# MainSheet.net
KiCad netlist of a schematic drawn in Altium Designer
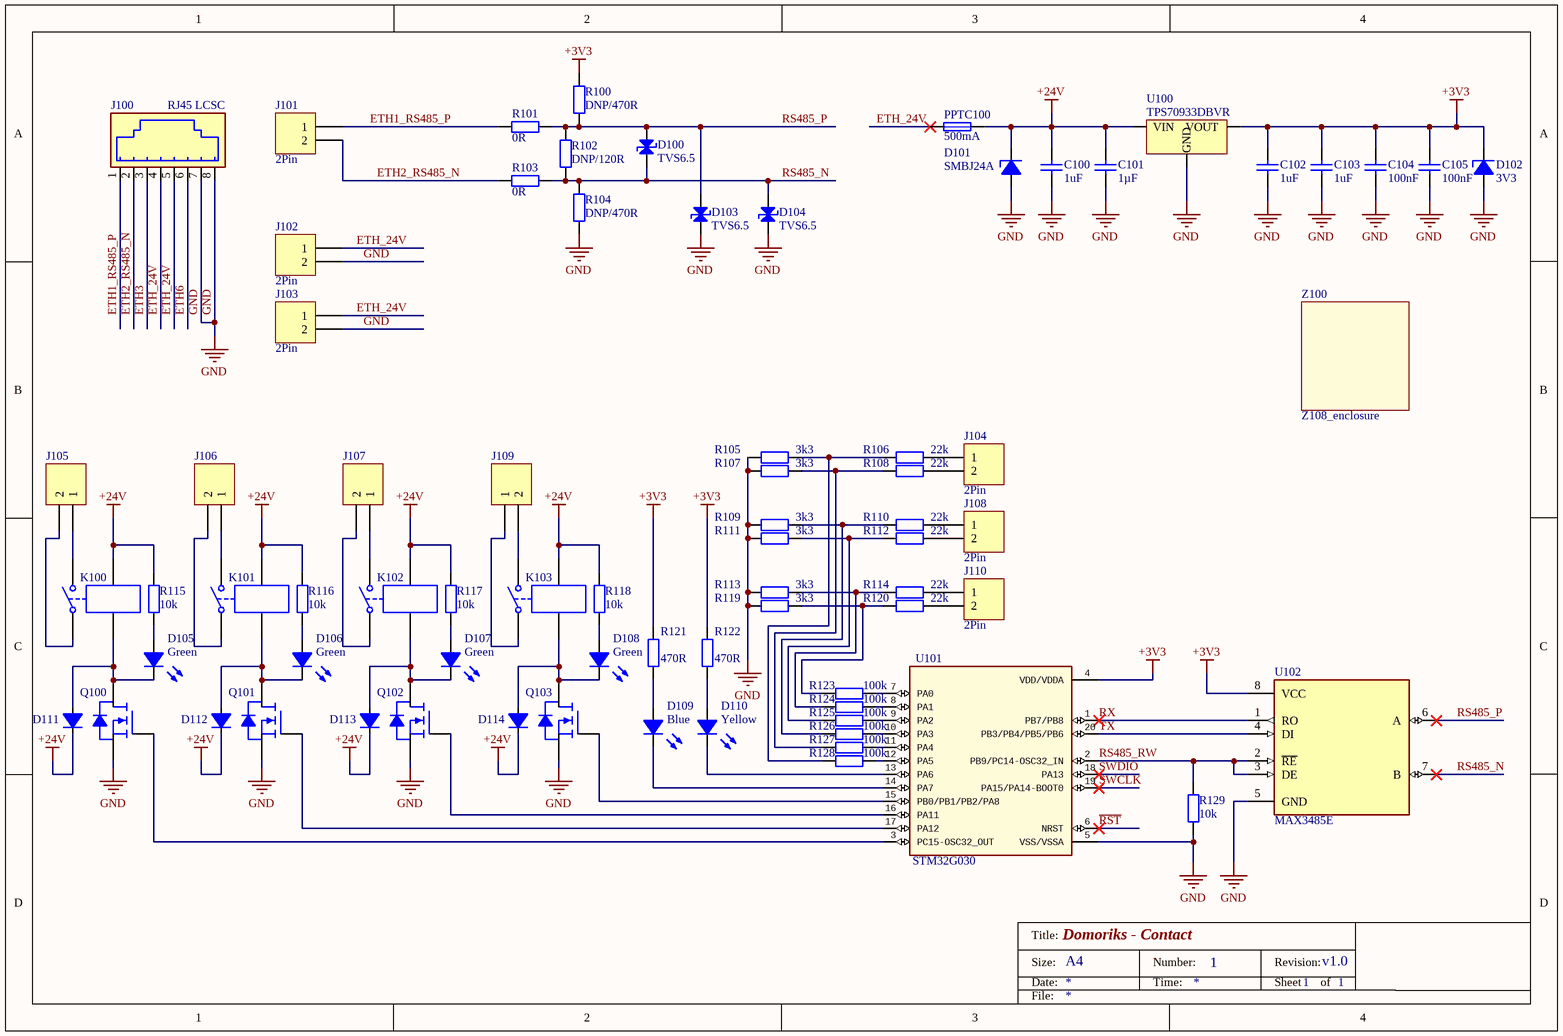
[diagram p0: MainSheet.SchDoc]

(export (version "E")
  (design (tool "Eeschema 10.0.6"))
  (components
    (comp (ref "C100") (value "1uF") (footprint "C0603") (libsource (lib "MyLib") (part "Capacitor")))
    (comp (ref "C101") (value "1µF") (footprint "C0603") (libsource (lib "MyLib") (part "Capacitor")))
    (comp (ref "C102") (value "1uF") (footprint "C0603") (libsource (lib "MyLib") (part "Capacitor")))
    (comp (ref "C103") (value "1uF") (footprint "C0603") (libsource (lib "MyLib") (part "Capacitor")))
    (comp (ref "C104") (value "100nF") (footprint "C0603") (libsource (lib "MyLib") (part "Capacitor")))
    (comp (ref "C105") (value "100nF") (footprint "C0603") (libsource (lib "MyLib") (part "Capacitor")))
    (comp (ref "D100") (value "TVS6.5") (footprint "SOD323") (libsource (lib "MyLib") (part "TVS Bi")))
    (comp (ref "D101") (value "SMBJ24A") (footprint "SMB") (libsource (lib "MyLib") (part "TVS Uni")))
    (comp (ref "D102") (value "3V3") (footprint "SOD323") (libsource (lib "MyLib") (part "TVS Uni")))
    (comp (ref "D103") (value "TVS6.5") (footprint "SOD323") (libsource (lib "MyLib") (part "TVS Bi")))
    (comp (ref "D104") (value "TVS6.5") (footprint "SOD323") (libsource (lib "MyLib") (part "TVS Bi")))
    (comp (ref "D105") (value "Green") (footprint "LED_0603_G") (libsource (lib "MyLib") (part "Led")))
    (comp (ref "D106") (value "Green") (footprint "LED_0603_G") (libsource (lib "MyLib") (part "Led")))
    (comp (ref "D107") (value "Green") (footprint "LED_0603_G") (libsource (lib "MyLib") (part "Led")))
    (comp (ref "D108") (value "Green") (footprint "LED_0603_G") (libsource (lib "MyLib") (part "Led")))
    (comp (ref "D109") (value "Blue") (footprint "LED_0603_B") (libsource (lib "MyLib") (part "Led")))
    (comp (ref "D110") (value "Yellow") (footprint "LED_0603_G") (libsource (lib "MyLib") (part "Led")))
    (comp (ref "D111") (value "Diode") (footprint "SOD323") (libsource (lib "MyLib") (part "Diode")))
    (comp (ref "D112") (value "Diode") (footprint "SOD323") (libsource (lib "MyLib") (part "Diode")))
    (comp (ref "D113") (value "Diode") (footprint "SOD323") (libsource (lib "MyLib") (part "Diode")))
    (comp (ref "D114") (value "Diode") (footprint "SOD323") (libsource (lib "MyLib") (part "Diode")))
    (comp (ref "J100")
      (value "RJ45 LCSC")
      (footprint "RJ45_RA")
      (description "Jack Modular Connector 8p8c (RJ45, Ethernet) Vertical Unshielded Cat5")
      (fields (field (name "MF") "Wurth Elektronik") (field (name "MP") "615008144221"))
      (libsource (lib "MyLib") (part "RJ45 LCSC"))
    )
    (comp (ref "J101") (value "2Pin") (footprint "WURTH_691216710002") (libsource (lib "") (part "2Pin_1")))
    (comp (ref "J102") (value "2Pin") (footprint "WURTH_691216710002") (libsource (lib "") (part "2Pin_1")))
    (comp (ref "J103") (value "2Pin") (footprint "WURTH_691216710002") (libsource (lib "") (part "2Pin_1")))
    (comp (ref "J104")
      (value "2Pin")
      (footprint "WURTH_691216710002")
      (libsource (lib "MyLib") (part "2Pin"))
    )
    (comp (ref "J105")
      (value "2Pin")
      (footprint "WURTH_691216910002")
      (libsource (lib "MyLib") (part "2Pin"))
    )
    (comp (ref "J106")
      (value "2Pin")
      (footprint "WURTH_691216910002")
      (libsource (lib "MyLib") (part "2Pin"))
    )
    (comp (ref "J107")
      (value "2Pin")
      (footprint "WURTH_691216910002")
      (libsource (lib "MyLib") (part "2Pin"))
    )
    (comp (ref "J108")
      (value "2Pin")
      (footprint "WURTH_691216710002")
      (libsource (lib "MyLib") (part "2Pin"))
    )
    (comp (ref "J109") (value "2Pin") (footprint "WURTH_691216910002") (libsource (lib "") (part "2Pin_2")))
    (comp (ref "J110")
      (value "2Pin")
      (footprint "WURTH_691216710002")
      (libsource (lib "MyLib") (part "2Pin"))
    )
    (comp (ref "K100")
      (value "Relay-SPST")
      (footprint "G5RL-1A-E-HR")
      (description "Single-Pole Single-Throw Relay")
      (fields (field (name "PUBLISHER") "Altium Limited"))
      (libsource (lib "MyLib") (part "Relay-SPST"))
    )
    (comp (ref "K101")
      (value "Relay-SPST")
      (footprint "G5RL-1A-E-HR")
      (description "Single-Pole Single-Throw Relay")
      (fields (field (name "PUBLISHER") "Altium Limited"))
      (libsource (lib "MyLib") (part "Relay-SPST"))
    )
    (comp (ref "K102")
      (value "Relay-SPST")
      (footprint "G5RL-1A-E-HR")
      (description "Single-Pole Single-Throw Relay")
      (fields (field (name "PUBLISHER") "Altium Limited"))
      (libsource (lib "MyLib") (part "Relay-SPST"))
    )
    (comp (ref "K103")
      (value "Relay-SPST")
      (footprint "G5RL-1A-E-HR")
      (description "Single-Pole Single-Throw Relay")
      (fields (field (name "PUBLISHER") "Altium Limited"))
      (libsource (lib "MyLib") (part "Relay-SPST"))
    )
    (comp (ref "PPTC100")
      (value "500mA")
      (footprint "PPTC1812")
      (description "Polymeric PTC Resettable Fuse 24V 500mA Ih Surface Mount 1812 _4532 Metric_, Concave")
      (fields (field (name "MP") "MINISMDC050F-2") (field (name "MF") "Littelfuse Inc."))
      (libsource (lib "MyLib") (part "PPTC"))
    )
    (comp (ref "Q100") (value "N-FET") (footprint "SOT323") (libsource (lib "MyLib") (part "N-FET")))
    (comp (ref "Q101") (value "N-FET") (footprint "SOT323") (libsource (lib "MyLib") (part "N-FET")))
    (comp (ref "Q102") (value "N-FET") (footprint "SOT323") (libsource (lib "MyLib") (part "N-FET")))
    (comp (ref "Q103") (value "N-FET") (footprint "SOT323") (libsource (lib "MyLib") (part "N-FET")))
    (comp (ref "R100") (value "DNP/470R") (footprint "R0603") (libsource (lib "MyLib") (part "Resistor")))
    (comp (ref "R101") (value "0R") (footprint "R0603") (libsource (lib "") (part "Resistor_1")))
    (comp (ref "R102") (value "DNP/120R") (footprint "R0603") (libsource (lib "MyLib") (part "Resistor")))
    (comp (ref "R103") (value "0R") (footprint "R0603") (libsource (lib "") (part "Resistor_1")))
    (comp (ref "R104") (value "DNP/470R") (footprint "R0603") (libsource (lib "MyLib") (part "Resistor")))
    (comp (ref "R105") (value "3k3") (footprint "R0603") (libsource (lib "") (part "Resistor_1")))
    (comp (ref "R106") (value "22k") (footprint "R0603") (libsource (lib "") (part "Resistor_1")))
    (comp (ref "R107") (value "3k3") (footprint "R0603") (libsource (lib "") (part "Resistor_1")))
    (comp (ref "R108") (value "22k") (footprint "R0603") (libsource (lib "") (part "Resistor_1")))
    (comp (ref "R109") (value "3k3") (footprint "R0603") (libsource (lib "") (part "Resistor_1")))
    (comp (ref "R110") (value "22k") (footprint "R0603") (libsource (lib "") (part "Resistor_1")))
    (comp (ref "R111") (value "3k3") (footprint "R0603") (libsource (lib "") (part "Resistor_1")))
    (comp (ref "R112") (value "22k") (footprint "R0603") (libsource (lib "") (part "Resistor_1")))
    (comp (ref "R113") (value "3k3") (footprint "R0603") (libsource (lib "") (part "Resistor_1")))
    (comp (ref "R114") (value "22k") (footprint "R0603") (libsource (lib "") (part "Resistor_1")))
    (comp (ref "R115") (value "10k") (footprint "R0402") (libsource (lib "MyLib") (part "Resistor")))
    (comp (ref "R116") (value "10k") (footprint "R0402") (libsource (lib "MyLib") (part "Resistor")))
    (comp (ref "R117") (value "10k") (footprint "R0402") (libsource (lib "MyLib") (part "Resistor")))
    (comp (ref "R118") (value "10k") (footprint "R0402") (libsource (lib "MyLib") (part "Resistor")))
    (comp (ref "R119") (value "3k3") (footprint "R0603") (libsource (lib "") (part "Resistor_1")))
    (comp (ref "R120") (value "22k") (footprint "R0603") (libsource (lib "") (part "Resistor_1")))
    (comp (ref "R121") (value "470R") (footprint "R0603") (libsource (lib "MyLib") (part "Resistor")))
    (comp (ref "R122") (value "470R") (footprint "R0603") (libsource (lib "MyLib") (part "Resistor")))
    (comp (ref "R123") (value "100k") (footprint "R0603") (libsource (lib "") (part "Resistor_1")))
    (comp (ref "R124") (value "100k") (footprint "R0603") (libsource (lib "") (part "Resistor_1")))
    (comp (ref "R125") (value "100k") (footprint "R0603") (libsource (lib "") (part "Resistor_1")))
    (comp (ref "R126") (value "100k") (footprint "R0603") (libsource (lib "") (part "Resistor_1")))
    (comp (ref "R127") (value "100k") (footprint "R0603") (libsource (lib "") (part "Resistor_1")))
    (comp (ref "R128") (value "100k") (footprint "R0603") (libsource (lib "") (part "Resistor_1")))
    (comp (ref "R129") (value "10k") (footprint "R0603") (libsource (lib "") (part "Resistor_1")))
    (comp (ref "U100")
      (value "TPS70933DBVR")
      (footprint "SOT-23-5")
      (fields (field (name "MP") "LP38690DT-5.0/NOPB") (field (name "MF") "Texas Instruments"))
      (libsource (lib "MyLib") (part "LDO"))
    )
    (comp (ref "U101")
      (value "STM32G030")
      (footprint "TSSOP20")
      (fields
        (field (name "MANUFACTURER_PART_NUMBER") "STM32G030F6P6TR")
        (field (name "COPYRIGHT") "Copyright (C) 2022 Ultra Librarian. All rights reserved.")
      )
      (libsource (lib "MyLib") (part "STM32G030"))
    )
    (comp (ref "U102")
      (value "MAX3485E")
      (footprint "SOIC-08_DOMO")
      (description "1/1 Transceiver Half RS422, RS485 8-SOIC")
      (fields (field (name "MF") "Maxim Integrated") (field (name "MP") "MAX3485EESA+T"))
      (libsource (lib "MyLib") (part "MAX3485E"))
    )
    (comp (ref "Z100")
      (value "Z108_enclosure")
      (footprint "Z108")
      (libsource (lib "MyLib") (part "Z108_enclosure"))
    )
  )
  (nets
    (net (code "1") (name "+3V3") (class "Default")
      (node (ref "C102") (pin "2") (pinfunction "2_2") (pintype "passive"))
      (node (ref "C103") (pin "2") (pinfunction "2_2") (pintype "passive"))
      (node (ref "C104") (pin "2") (pinfunction "2_2") (pintype "passive"))
      (node (ref "C105") (pin "2") (pinfunction "2_2") (pintype "passive"))
      (node (ref "D102") (pin "1") (pinfunction "1_1") (pintype "passive"))
      (node (ref "R100") (pin "2") (pinfunction "2_2") (pintype "passive"))
      (node (ref "R121") (pin "2") (pinfunction "2_2") (pintype "passive"))
      (node (ref "R122") (pin "2") (pinfunction "2_2") (pintype "passive"))
      (node (ref "U100") (pin "5") (pinfunction "VOUT_5") (pintype "power_in"))
      (node (ref "U101") (pin "4") (pinfunction "VDD/VDDA_4") (pintype "power_in"))
      (node (ref "U102") (pin "8") (pinfunction "VCC_8") (pintype "power_in"))
    )
    (net (code "2") (name "+24V") (class "Default")
      (node (ref "C100") (pin "2") (pinfunction "2_2") (pintype "passive"))
      (node (ref "C101") (pin "2") (pinfunction "2_2") (pintype "passive"))
      (node (ref "D101") (pin "1") (pinfunction "1_1") (pintype "passive"))
      (node (ref "D111") (pin "1") (pinfunction "1_1") (pintype "passive"))
      (node (ref "D112") (pin "1") (pinfunction "1_1") (pintype "passive"))
      (node (ref "D113") (pin "1") (pinfunction "1_1") (pintype "passive"))
      (node (ref "D114") (pin "1") (pinfunction "1_1") (pintype "passive"))
      (node (ref "K100") (pin "2") (pinfunction "2_2") (pintype "passive"))
      (node (ref "K101") (pin "2") (pinfunction "2_2") (pintype "passive"))
      (node (ref "K102") (pin "2") (pinfunction "2_2") (pintype "passive"))
      (node (ref "K103") (pin "2") (pinfunction "2_2") (pintype "passive"))
      (node (ref "PPTC100") (pin "2") (pinfunction "2_2") (pintype "passive"))
      (node (ref "R115") (pin "2") (pinfunction "2_2") (pintype "passive"))
      (node (ref "R116") (pin "2") (pinfunction "2_2") (pintype "passive"))
      (node (ref "R117") (pin "2") (pinfunction "2_2") (pintype "passive"))
      (node (ref "R118") (pin "2") (pinfunction "2_2") (pintype "passive"))
      (node (ref "U100") (pin "1") (pinfunction "VIN_1") (pintype "power_in"))
    )
    (net (code "3") (name "/ETH1_RS485_P") (class "Default")
      (node (ref "J100") (pin "1") (pinfunction "8_1") (pintype "passive"))
      (node (ref "J101") (pin "1") (pinfunction "1_1") (pintype "passive"))
      (node (ref "R101") (pin "1") (pinfunction "1_1") (pintype "passive"))
    )
    (net (code "4") (name "/ETH2_RS485_N") (class "Default")
      (node (ref "J100") (pin "2") (pinfunction "7_2") (pintype "passive"))
      (node (ref "J101") (pin "2") (pinfunction "2_2") (pintype "passive"))
      (node (ref "R103") (pin "1") (pinfunction "1_1") (pintype "passive"))
    )
    (net (code "5") (name "/ETH3") (class "Default")
      (node (ref "J100") (pin "3") (pinfunction "6_3") (pintype "passive"))
    )
    (net (code "6") (name "/ETH6") (class "Default")
      (node (ref "J100") (pin "6") (pinfunction "3_6") (pintype "passive"))
    )
    (net (code "7") (name "/ETH_24V") (class "Default")
      (node (ref "J100") (pin "4") (pinfunction "5_4") (pintype "passive"))
      (node (ref "J100") (pin "5") (pinfunction "4_5") (pintype "passive"))
      (node (ref "J102") (pin "1") (pinfunction "1_1") (pintype "passive"))
      (node (ref "J103") (pin "1") (pinfunction "1_1") (pintype "passive"))
      (node (ref "PPTC100") (pin "1") (pinfunction "1_1") (pintype "passive"))
    )
    (net (code "8") (name "/RS485_N") (class "Default")
      (node (ref "D100") (pin "1") (pinfunction "1_1") (pintype "passive"))
      (node (ref "D104") (pin "2") (pinfunction "2_2") (pintype "passive"))
      (node (ref "R102") (pin "1") (pinfunction "1_1") (pintype "passive"))
      (node (ref "R103") (pin "2") (pinfunction "2_2") (pintype "passive"))
      (node (ref "R104") (pin "2") (pinfunction "2_2") (pintype "passive"))
      (node (ref "U102") (pin "7") (pinfunction "B_7") (pintype "bidirectional"))
    )
    (net (code "9") (name "/RS485_P") (class "Default")
      (node (ref "D100") (pin "2") (pinfunction "2_2") (pintype "passive"))
      (node (ref "D103") (pin "2") (pinfunction "2_2") (pintype "passive"))
      (node (ref "R100") (pin "1") (pinfunction "1_1") (pintype "passive"))
      (node (ref "R101") (pin "2") (pinfunction "2_2") (pintype "passive"))
      (node (ref "R102") (pin "2") (pinfunction "2_2") (pintype "passive"))
      (node (ref "U102") (pin "6") (pinfunction "A_6") (pintype "bidirectional"))
    )
    (net (code "10") (name "/RS485_RW") (class "Default")
      (node (ref "R129") (pin "2") (pinfunction "2_2") (pintype "passive"))
      (node (ref "U101") (pin "2") (pinfunction "PB9/PC14-OSC32_IN_2") (pintype "bidirectional"))
      (node (ref "U102") (pin "2") (pinfunction "~{RE}_2") (pintype "input"))
      (node (ref "U102") (pin "3") (pinfunction "DE_3") (pintype "input"))
    )
    (net (code "11") (name "/RX") (class "Default")
      (node (ref "U101") (pin "1") (pinfunction "PB7/PB8_1") (pintype "bidirectional"))
      (node (ref "U102") (pin "1") (pinfunction "RO_1") (pintype "output"))
    )
    (net (code "12") (name "/SWCLK") (class "Default")
      (node (ref "U101") (pin "19") (pinfunction "PA15/PA14-BOOT0_19") (pintype "bidirectional+no_connect"))
    )
    (net (code "13") (name "/SWDIO") (class "Default")
      (node (ref "U101") (pin "18") (pinfunction "PA13_18") (pintype "bidirectional+no_connect"))
    )
    (net (code "14") (name "/TX") (class "Default")
      (node (ref "U101") (pin "20") (pinfunction "PB3/PB4/PB5/PB6_20") (pintype "bidirectional"))
      (node (ref "U102") (pin "4") (pinfunction "DI_4") (pintype "input"))
    )
    (net (code "15") (name "/~{RST}") (class "Default")
      (node (ref "U101") (pin "6") (pinfunction "NRST_6") (pintype "bidirectional+no_connect"))
    )
    (net (code "16") (name "GND") (class "Default")
      (node (ref "C100") (pin "1") (pinfunction "1_1") (pintype "passive"))
      (node (ref "C101") (pin "1") (pinfunction "1_1") (pintype "passive"))
      (node (ref "C102") (pin "1") (pinfunction "1_1") (pintype "passive"))
      (node (ref "C103") (pin "1") (pinfunction "1_1") (pintype "passive"))
      (node (ref "C104") (pin "1") (pinfunction "1_1") (pintype "passive"))
      (node (ref "C105") (pin "1") (pinfunction "1_1") (pintype "passive"))
      (node (ref "D101") (pin "2") (pinfunction "2_2") (pintype "passive"))
      (node (ref "D102") (pin "2") (pinfunction "2_2") (pintype "passive"))
      (node (ref "D103") (pin "1") (pinfunction "1_1") (pintype "passive"))
      (node (ref "D104") (pin "1") (pinfunction "1_1") (pintype "passive"))
      (node (ref "J100") (pin "7") (pinfunction "2_7") (pintype "passive"))
      (node (ref "J100") (pin "8") (pinfunction "1_8") (pintype "passive"))
      (node (ref "J102") (pin "2") (pinfunction "2_2") (pintype "passive"))
      (node (ref "J103") (pin "2") (pinfunction "2_2") (pintype "passive"))
      (node (ref "Q100") (pin "2") (pinfunction "S_2") (pintype "passive"))
      (node (ref "Q101") (pin "2") (pinfunction "S_2") (pintype "passive"))
      (node (ref "Q102") (pin "2") (pinfunction "S_2") (pintype "passive"))
      (node (ref "Q103") (pin "2") (pinfunction "S_2") (pintype "passive"))
      (node (ref "R104") (pin "1") (pinfunction "1_1") (pintype "passive"))
      (node (ref "R105") (pin "1") (pinfunction "1_1") (pintype "passive"))
      (node (ref "R107") (pin "1") (pinfunction "1_1") (pintype "passive"))
      (node (ref "R109") (pin "1") (pinfunction "1_1") (pintype "passive"))
      (node (ref "R111") (pin "1") (pinfunction "1_1") (pintype "passive"))
      (node (ref "R113") (pin "1") (pinfunction "1_1") (pintype "passive"))
      (node (ref "R119") (pin "1") (pinfunction "1_1") (pintype "passive"))
      (node (ref "R129") (pin "1") (pinfunction "1_1") (pintype "passive"))
      (node (ref "U100") (pin "2") (pinfunction "GND_2") (pintype "passive"))
      (node (ref "U101") (pin "5") (pinfunction "VSS/VSSA_5") (pintype "power_in"))
      (node (ref "U102") (pin "5") (pinfunction "GND_5") (pintype "power_in"))
    )
    (net (code "17") (name "Net-(D105-Pad1)") (class "Default")
      (node (ref "D105") (pin "1") (pinfunction "1_1") (pintype "passive"))
      (node (ref "R115") (pin "1") (pinfunction "1_1") (pintype "passive"))
    )
    (net (code "18") (name "Net-(D106-Pad1)") (class "Default")
      (node (ref "D106") (pin "1") (pinfunction "1_1") (pintype "passive"))
      (node (ref "R116") (pin "1") (pinfunction "1_1") (pintype "passive"))
    )
    (net (code "19") (name "Net-(D107-Pad1)") (class "Default")
      (node (ref "D107") (pin "1") (pinfunction "1_1") (pintype "passive"))
      (node (ref "R117") (pin "1") (pinfunction "1_1") (pintype "passive"))
    )
    (net (code "20") (name "Net-(D108-Pad1)") (class "Default")
      (node (ref "D108") (pin "1") (pinfunction "1_1") (pintype "passive"))
      (node (ref "R118") (pin "1") (pinfunction "1_1") (pintype "passive"))
    )
    (net (code "21") (name "Net-(D109-Pad1)") (class "Default")
      (node (ref "D109") (pin "1") (pinfunction "1_1") (pintype "passive"))
      (node (ref "R121") (pin "1") (pinfunction "1_1") (pintype "passive"))
    )
    (net (code "22") (name "Net-(D110-Pad1)") (class "Default")
      (node (ref "D110") (pin "1") (pinfunction "1_1") (pintype "passive"))
      (node (ref "R122") (pin "1") (pinfunction "1_1") (pintype "passive"))
    )
    (net (code "23") (name "Net-(J104-Pad1)") (class "Default")
      (node (ref "J104") (pin "1") (pinfunction "1_1") (pintype "passive"))
      (node (ref "R106") (pin "2") (pinfunction "2_2") (pintype "passive"))
    )
    (net (code "24") (name "Net-(J104-Pad2)") (class "Default")
      (node (ref "J104") (pin "2") (pinfunction "2_2") (pintype "passive"))
      (node (ref "R108") (pin "2") (pinfunction "2_2") (pintype "passive"))
    )
    (net (code "25") (name "Net-(J105-Pad1)") (class "Default")
      (node (ref "J105") (pin "1") (pinfunction "1_1") (pintype "passive"))
      (node (ref "K100") (pin "3") (pinfunction "3_3") (pintype "passive"))
    )
    (net (code "26") (name "Net-(J105-Pad2)") (class "Default")
      (node (ref "J105") (pin "2") (pinfunction "2_2") (pintype "passive"))
      (node (ref "K100") (pin "4") (pinfunction "4_4") (pintype "passive"))
    )
    (net (code "27") (name "Net-(J106-Pad1)") (class "Default")
      (node (ref "J106") (pin "1") (pinfunction "1_1") (pintype "passive"))
      (node (ref "K101") (pin "3") (pinfunction "3_3") (pintype "passive"))
    )
    (net (code "28") (name "Net-(J106-Pad2)") (class "Default")
      (node (ref "J106") (pin "2") (pinfunction "2_2") (pintype "passive"))
      (node (ref "K101") (pin "4") (pinfunction "4_4") (pintype "passive"))
    )
    (net (code "29") (name "Net-(J107-Pad1)") (class "Default")
      (node (ref "J107") (pin "1") (pinfunction "1_1") (pintype "passive"))
      (node (ref "K102") (pin "3") (pinfunction "3_3") (pintype "passive"))
    )
    (net (code "30") (name "Net-(J107-Pad2)") (class "Default")
      (node (ref "J107") (pin "2") (pinfunction "2_2") (pintype "passive"))
      (node (ref "K102") (pin "4") (pinfunction "4_4") (pintype "passive"))
    )
    (net (code "31") (name "Net-(J108-Pad1)") (class "Default")
      (node (ref "J108") (pin "1") (pinfunction "1_1") (pintype "passive"))
      (node (ref "R110") (pin "2") (pinfunction "2_2") (pintype "passive"))
    )
    (net (code "32") (name "Net-(J108-Pad2)") (class "Default")
      (node (ref "J108") (pin "2") (pinfunction "2_2") (pintype "passive"))
      (node (ref "R112") (pin "2") (pinfunction "2_2") (pintype "passive"))
    )
    (net (code "33") (name "Net-(J109-Pad1)") (class "Default")
      (node (ref "J109") (pin "1") (pinfunction "1_1") (pintype "passive"))
      (node (ref "K103") (pin "4") (pinfunction "4_4") (pintype "passive"))
    )
    (net (code "34") (name "Net-(J109-Pad2)") (class "Default")
      (node (ref "J109") (pin "2") (pinfunction "2_2") (pintype "passive"))
      (node (ref "K103") (pin "3") (pinfunction "3_3") (pintype "passive"))
    )
    (net (code "35") (name "Net-(J110-Pad1)") (class "Default")
      (node (ref "J110") (pin "1") (pinfunction "1_1") (pintype "passive"))
      (node (ref "R114") (pin "2") (pinfunction "2_2") (pintype "passive"))
    )
    (net (code "36") (name "Net-(J110-Pad2)") (class "Default")
      (node (ref "J110") (pin "2") (pinfunction "2_2") (pintype "passive"))
      (node (ref "R120") (pin "2") (pinfunction "2_2") (pintype "passive"))
    )
    (net (code "37") (name "Net-(Q100-D)") (class "Default")
      (node (ref "D105") (pin "2") (pinfunction "2_2") (pintype "passive"))
      (node (ref "D111") (pin "2") (pinfunction "2_2") (pintype "passive"))
      (node (ref "K100") (pin "1") (pinfunction "1_1") (pintype "passive"))
      (node (ref "Q100") (pin "3") (pinfunction "D_3") (pintype "passive"))
    )
    (net (code "38") (name "Net-(Q100-G)") (class "Default")
      (node (ref "Q100") (pin "1") (pinfunction "G_1") (pintype "passive"))
      (node (ref "U101") (pin "3") (pinfunction "PC15-OSC32_OUT_3") (pintype "bidirectional"))
    )
    (net (code "39") (name "Net-(Q101-D)") (class "Default")
      (node (ref "D106") (pin "2") (pinfunction "2_2") (pintype "passive"))
      (node (ref "D112") (pin "2") (pinfunction "2_2") (pintype "passive"))
      (node (ref "K101") (pin "1") (pinfunction "1_1") (pintype "passive"))
      (node (ref "Q101") (pin "3") (pinfunction "D_3") (pintype "passive"))
    )
    (net (code "40") (name "Net-(Q101-G)") (class "Default")
      (node (ref "Q101") (pin "1") (pinfunction "G_1") (pintype "passive"))
      (node (ref "U101") (pin "17") (pinfunction "PA12_17") (pintype "bidirectional"))
    )
    (net (code "41") (name "Net-(Q102-D)") (class "Default")
      (node (ref "D107") (pin "2") (pinfunction "2_2") (pintype "passive"))
      (node (ref "D113") (pin "2") (pinfunction "2_2") (pintype "passive"))
      (node (ref "K102") (pin "1") (pinfunction "1_1") (pintype "passive"))
      (node (ref "Q102") (pin "3") (pinfunction "D_3") (pintype "passive"))
    )
    (net (code "42") (name "Net-(Q102-G)") (class "Default")
      (node (ref "Q102") (pin "1") (pinfunction "G_1") (pintype "passive"))
      (node (ref "U101") (pin "16") (pinfunction "PA11_16") (pintype "bidirectional"))
    )
    (net (code "43") (name "Net-(Q103-D)") (class "Default")
      (node (ref "D108") (pin "2") (pinfunction "2_2") (pintype "passive"))
      (node (ref "D114") (pin "2") (pinfunction "2_2") (pintype "passive"))
      (node (ref "K103") (pin "1") (pinfunction "1_1") (pintype "passive"))
      (node (ref "Q103") (pin "3") (pinfunction "D_3") (pintype "passive"))
    )
    (net (code "44") (name "Net-(Q103-G)") (class "Default")
      (node (ref "Q103") (pin "1") (pinfunction "G_1") (pintype "passive"))
      (node (ref "U101") (pin "15") (pinfunction "PB0/PB1/PB2/PA8_15") (pintype "bidirectional"))
    )
    (net (code "45") (name "Net-(R105-Pad2)") (class "Default")
      (node (ref "R105") (pin "2") (pinfunction "2_2") (pintype "passive"))
      (node (ref "R106") (pin "1") (pinfunction "1_1") (pintype "passive"))
      (node (ref "R128") (pin "1") (pinfunction "1_1") (pintype "passive"))
    )
    (net (code "46") (name "Net-(R107-Pad2)") (class "Default")
      (node (ref "R107") (pin "2") (pinfunction "2_2") (pintype "passive"))
      (node (ref "R108") (pin "1") (pinfunction "1_1") (pintype "passive"))
      (node (ref "R127") (pin "1") (pinfunction "1_1") (pintype "passive"))
    )
    (net (code "47") (name "Net-(R109-Pad2)") (class "Default")
      (node (ref "R109") (pin "2") (pinfunction "2_2") (pintype "passive"))
      (node (ref "R110") (pin "1") (pinfunction "1_1") (pintype "passive"))
      (node (ref "R126") (pin "1") (pinfunction "1_1") (pintype "passive"))
    )
    (net (code "48") (name "Net-(R111-Pad2)") (class "Default")
      (node (ref "R111") (pin "2") (pinfunction "2_2") (pintype "passive"))
      (node (ref "R112") (pin "1") (pinfunction "1_1") (pintype "passive"))
      (node (ref "R125") (pin "1") (pinfunction "1_1") (pintype "passive"))
    )
    (net (code "49") (name "Net-(R113-Pad2)") (class "Default")
      (node (ref "R113") (pin "2") (pinfunction "2_2") (pintype "passive"))
      (node (ref "R114") (pin "1") (pinfunction "1_1") (pintype "passive"))
      (node (ref "R124") (pin "1") (pinfunction "1_1") (pintype "passive"))
    )
    (net (code "50") (name "Net-(R119-Pad2)") (class "Default")
      (node (ref "R119") (pin "2") (pinfunction "2_2") (pintype "passive"))
      (node (ref "R120") (pin "1") (pinfunction "1_1") (pintype "passive"))
      (node (ref "R123") (pin "1") (pinfunction "1_1") (pintype "passive"))
    )
    (net (code "51") (name "Net-(U101-PA0)") (class "Default")
      (node (ref "R123") (pin "2") (pinfunction "2_2") (pintype "passive"))
      (node (ref "U101") (pin "7") (pinfunction "PA0_7") (pintype "bidirectional"))
    )
    (net (code "52") (name "Net-(U101-PA1)") (class "Default")
      (node (ref "R124") (pin "2") (pinfunction "2_2") (pintype "passive"))
      (node (ref "U101") (pin "8") (pinfunction "PA1_8") (pintype "bidirectional"))
    )
    (net (code "53") (name "Net-(U101-PA2)") (class "Default")
      (node (ref "R125") (pin "2") (pinfunction "2_2") (pintype "passive"))
      (node (ref "U101") (pin "9") (pinfunction "PA2_9") (pintype "bidirectional"))
    )
    (net (code "54") (name "Net-(U101-PA3)") (class "Default")
      (node (ref "R126") (pin "2") (pinfunction "2_2") (pintype "passive"))
      (node (ref "U101") (pin "10") (pinfunction "PA3_10") (pintype "bidirectional"))
    )
    (net (code "55") (name "Net-(U101-PA4)") (class "Default")
      (node (ref "R127") (pin "2") (pinfunction "2_2") (pintype "passive"))
      (node (ref "U101") (pin "11") (pinfunction "PA4_11") (pintype "bidirectional"))
    )
    (net (code "56") (name "Net-(U101-PA5)") (class "Default")
      (node (ref "R128") (pin "2") (pinfunction "2_2") (pintype "passive"))
      (node (ref "U101") (pin "12") (pinfunction "PA5_12") (pintype "bidirectional"))
    )
    (net (code "57") (name "Net-(U101-PA6)") (class "Default")
      (node (ref "D110") (pin "2") (pinfunction "2_2") (pintype "passive"))
      (node (ref "U101") (pin "13") (pinfunction "PA6_13") (pintype "bidirectional"))
    )
    (net (code "58") (name "Net-(U101-PA7)") (class "Default")
      (node (ref "D109") (pin "2") (pinfunction "2_2") (pintype "passive"))
      (node (ref "U101") (pin "14") (pinfunction "PA7_14") (pintype "bidirectional"))
    )
  )
)
